# semiflex-1.net
KiCad netlist of a schematic drawn in Altium Designer
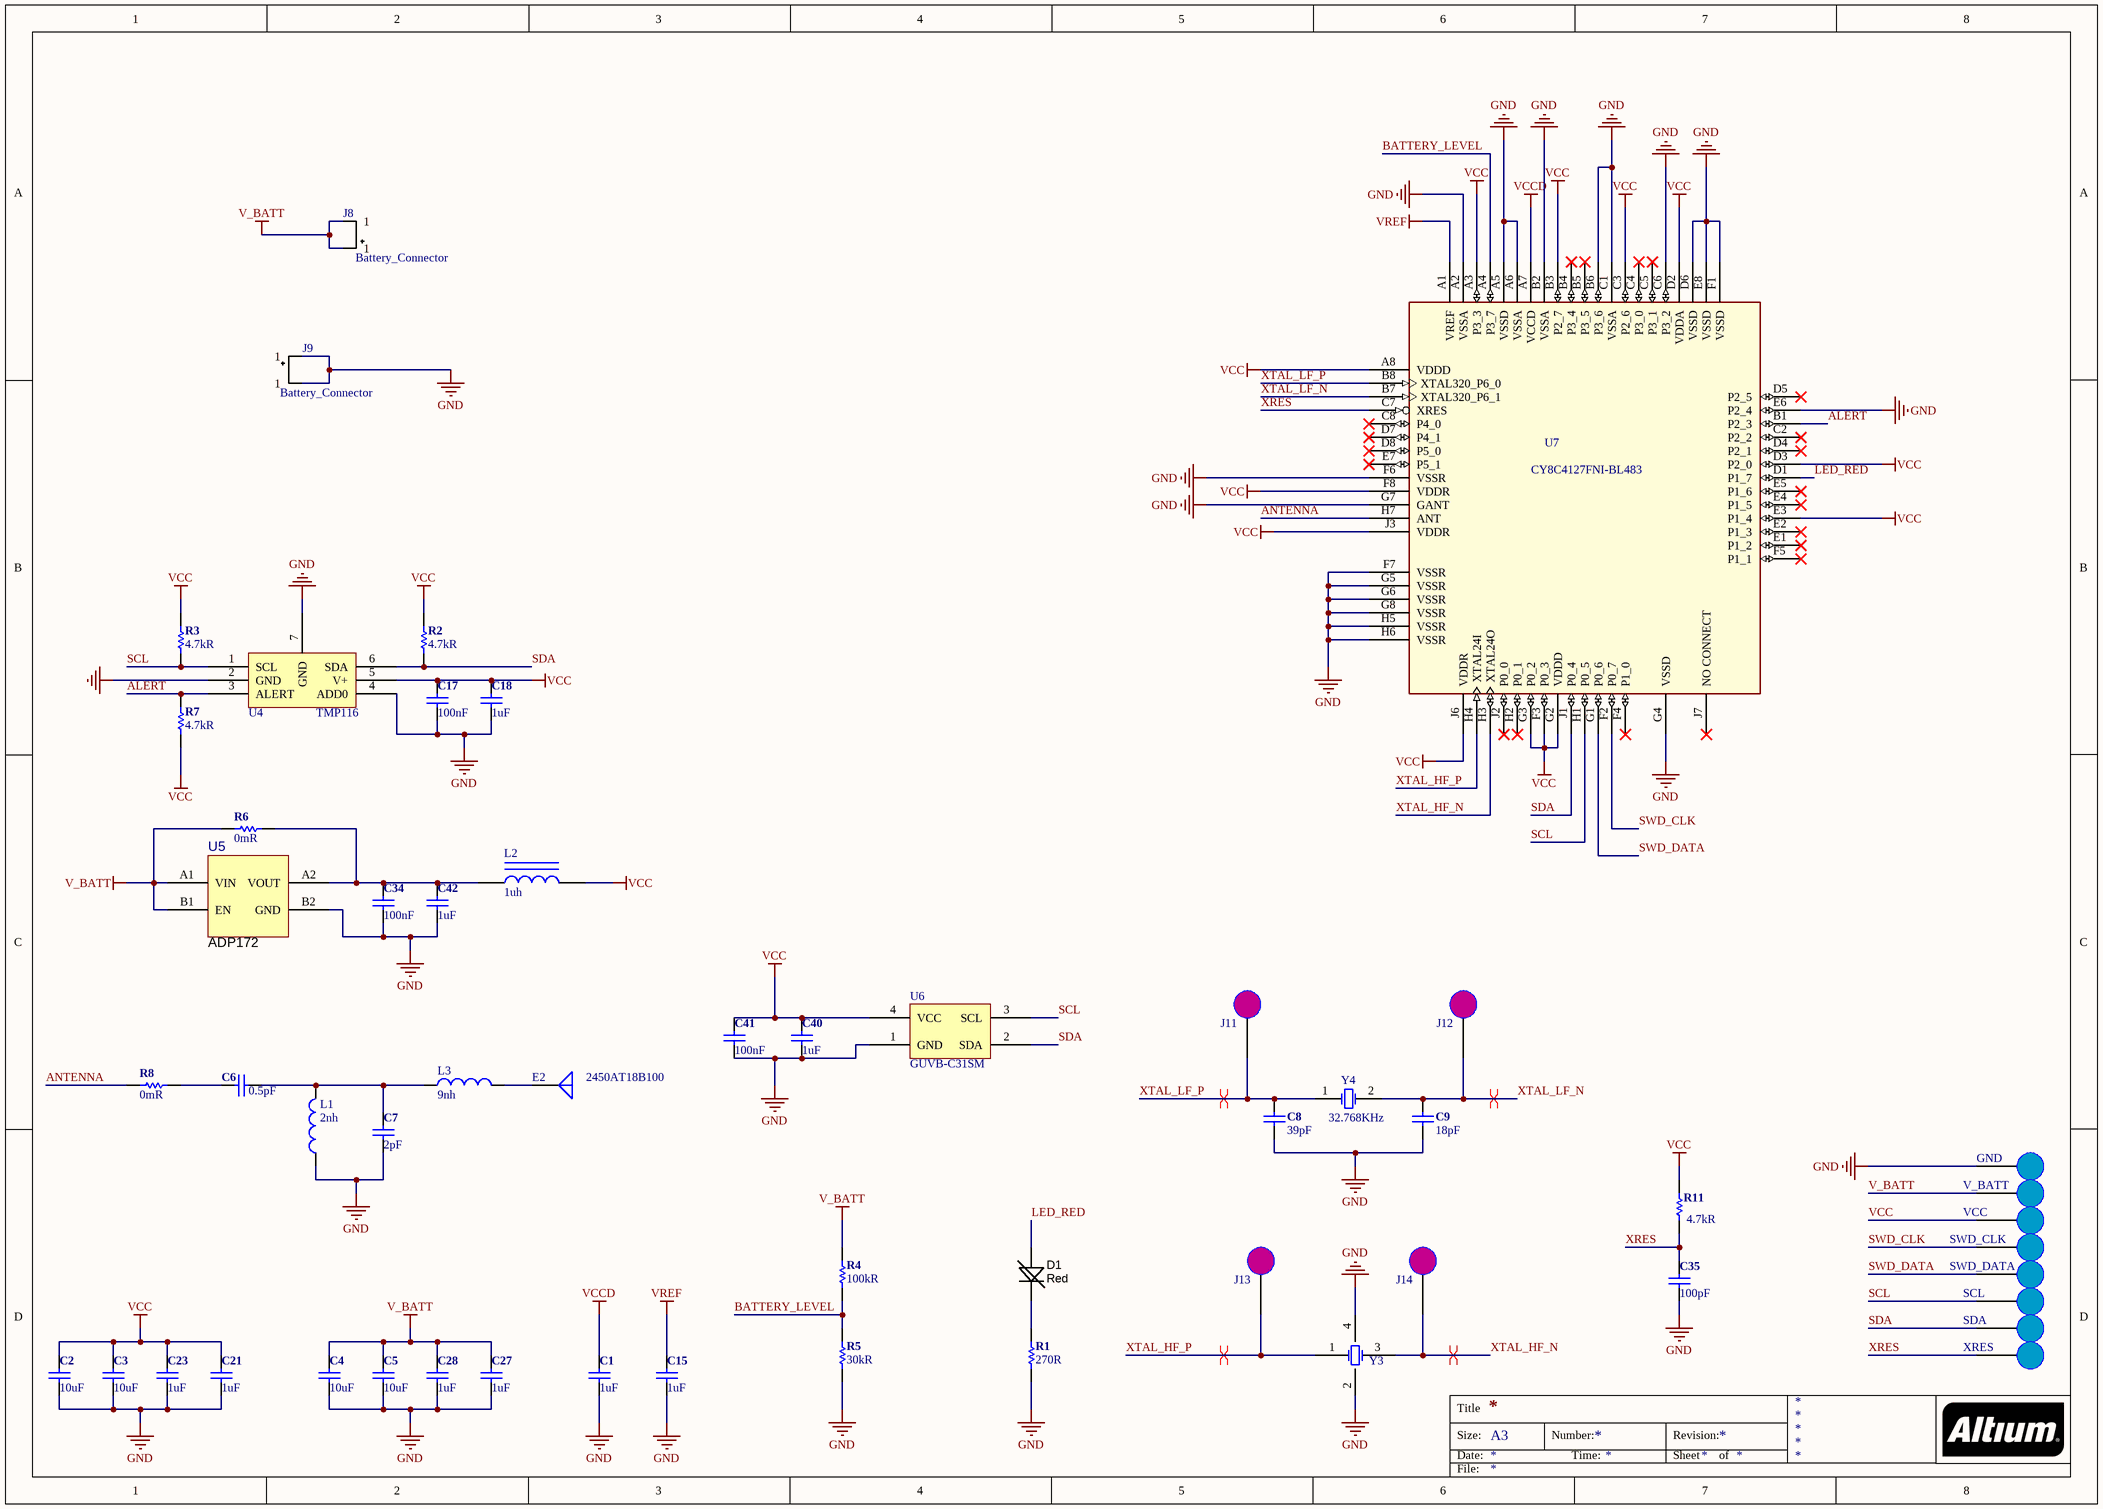
[diagram p0: semiflex-1.SchDoc]

(export (version "E")
  (design (tool "Eeschema 10.0.6"))
  (components
    (comp (ref "C1")
      (value "1uF")
      (footprint "CAP_0201(0603)_M")
      (description "___ OHM ___ mW 0201(0603) SMD")
      (fields
        (field (name "MANUFACTURER") "Murata")
        (field (name "MANUFACTURER PART NUMBER") "GRM033C81A105ME05D")
      )
      (libsource (lib "tempsensor") (part "C-0201(0603)"))
    )
    (comp (ref "C2")
      (value "10uF")
      (footprint "CAP_0402(1005)_M")
      (description "___ OHM ___ mW 0402(1005) SMD")
      (fields
        (field (name "MANUFACTURER") "Murata")
        (field (name "MANUFACTURER PART NUMBER") "GRM155R60J106ME15D")
      )
      (libsource (lib "tempsensor") (part "C-0402(1005)"))
    )
    (comp (ref "C3")
      (value "10uF")
      (footprint "CAP_0402(1005)_M")
      (description "___ OHM ___ mW 0402(1005) SMD")
      (fields
        (field (name "MANUFACTURER") "Murata")
        (field (name "MANUFACTURER PART NUMBER") "GRM155R60J106ME15D")
      )
      (libsource (lib "tempsensor") (part "C-0402(1005)"))
    )
    (comp (ref "C4")
      (value "10uF")
      (footprint "CAP_0402(1005)_M")
      (description "___ OHM ___ mW 0402(1005) SMD")
      (fields
        (field (name "MANUFACTURER") "Murata")
        (field (name "MANUFACTURER PART NUMBER") "GRM155R60J106ME15D")
      )
      (libsource (lib "tempsensor") (part "C-0402(1005)"))
    )
    (comp (ref "C5")
      (value "10uF")
      (footprint "CAP_0402(1005)_M")
      (description "___ OHM ___ mW 0402(1005) SMD")
      (fields
        (field (name "MANUFACTURER") "Murata")
        (field (name "MANUFACTURER PART NUMBER") "GRM155R60J106ME15D")
      )
      (libsource (lib "tempsensor") (part "C-0402(1005)"))
    )
    (comp (ref "C6")
      (value "0.5pF")
      (footprint "CAP_0402(1005)_M")
      (description "___ OHM ___ mW 0402(1005) SMD")
      (fields
        (field (name "MANUFACTURER") "Murata")
        (field (name "MANUFACTURER PART NUMBER") "GJM1555C1HR50WB01D")
      )
      (libsource (lib "tempsensor") (part "C-0402(1005)"))
    )
    (comp (ref "C7")
      (value "2pF")
      (footprint "CAP_0402(1005)_M")
      (description "___ OHM ___ mW 0402(1005) SMD")
      (fields
        (field (name "MANUFACTURER") "Murata")
        (field (name "MANUFACTURER PART NUMBER") "GJM1555C1H2R0BB01D")
      )
      (libsource (lib "tempsensor") (part "C-0402(1005)"))
    )
    (comp (ref "C8")
      (value "39pF")
      (footprint "CAP_0402(1005)_M")
      (description "___ OHM ___ mW 0402(1005) SMD")
      (fields
        (field (name "MANUFACTURER") "KEMET")
        (field (name "MANUFACTURER PART NUMBER") "CBR04C390F5GAC")
      )
      (libsource (lib "tempsensor") (part "C-0402(1005)"))
    )
    (comp (ref "C9")
      (value "18pF")
      (footprint "CAP_0402(1005)_M")
      (description "___ OHM ___ mW 0402(1005) SMD")
      (fields
        (field (name "MANUFACTURER") "Murata")
        (field (name "MANUFACTURER PART NUMBER") "GJM1555C1H180FB01D")
      )
      (libsource (lib "tempsensor") (part "C-0402(1005)"))
    )
    (comp (ref "C15")
      (value "1uF")
      (footprint "CAP_0201(0603)_M")
      (description "___ OHM ___ mW 0201(0603) SMD")
      (fields
        (field (name "MANUFACTURER") "Murata")
        (field (name "MANUFACTURER PART NUMBER") "GRM033C81A105ME05D")
      )
      (libsource (lib "tempsensor") (part "C-0201(0603)"))
    )
    (comp (ref "C17")
      (value "100nF")
      (footprint "CAP_0201(0603)_M")
      (description "___ OHM ___ mW 0201(0603) SMD")
      (fields
        (field (name "MANUFACTURER") "Murata")
        (field (name "MANUFACTURER PART NUMBER") "GRM033R61A104ME15D")
      )
      (libsource (lib "tempsensor") (part "C-0201(0603)"))
    )
    (comp (ref "C18")
      (value "1uF")
      (footprint "CAP_0201(0603)_M")
      (description "___ OHM ___ mW 0201(0603) SMD")
      (fields
        (field (name "MANUFACTURER") "Murata")
        (field (name "MANUFACTURER PART NUMBER") "GRM033C81A105ME05D")
      )
      (libsource (lib "tempsensor") (part "C-0201(0603)"))
    )
    (comp (ref "C21")
      (value "1uF")
      (footprint "CAP_0201(0603)_M")
      (description "___ OHM ___ mW 0201(0603) SMD")
      (fields
        (field (name "MANUFACTURER") "Murata")
        (field (name "MANUFACTURER PART NUMBER") "GRM033C81A105ME05D")
      )
      (libsource (lib "tempsensor") (part "C-0201(0603)"))
    )
    (comp (ref "C23")
      (value "1uF")
      (footprint "CAP_0201(0603)_M")
      (description "___ OHM ___ mW 0201(0603) SMD")
      (fields
        (field (name "MANUFACTURER") "Murata")
        (field (name "MANUFACTURER PART NUMBER") "GRM033C81A105ME05D")
      )
      (libsource (lib "tempsensor") (part "C-0201(0603)"))
    )
    (comp (ref "C27")
      (value "1uF")
      (footprint "CAP_0201(0603)_M")
      (description "___ OHM ___ mW 0201(0603) SMD")
      (fields
        (field (name "MANUFACTURER") "Murata")
        (field (name "MANUFACTURER PART NUMBER") "GRM033C81A105ME05D")
      )
      (libsource (lib "tempsensor") (part "C-0201(0603)"))
    )
    (comp (ref "C28")
      (value "1uF")
      (footprint "CAP_0201(0603)_M")
      (description "___ OHM ___ mW 0201(0603) SMD")
      (fields
        (field (name "MANUFACTURER") "Murata")
        (field (name "MANUFACTURER PART NUMBER") "GRM033C81A105ME05D")
      )
      (libsource (lib "tempsensor") (part "C-0201(0603)"))
    )
    (comp (ref "C34")
      (value "100nF")
      (footprint "CAP_0201(0603)_M")
      (description "___ OHM ___ mW 0201(0603) SMD")
      (fields
        (field (name "MANUFACTURER") "Murata")
        (field (name "MANUFACTURER PART NUMBER") "GRM033R61A104ME15D")
      )
      (libsource (lib "tempsensor") (part "C-0201(0603)"))
    )
    (comp (ref "C35")
      (value "100pF")
      (footprint "CAP_0201(0603)_M")
      (description "___ OHM ___ mW 0201(0603) SMD")
      (fields
        (field (name "MANUFACTURER") "Murata")
        (field (name "MANUFACTURER PART NUMBER") "GRM033R71C101KA01D")
      )
      (libsource (lib "tempsensor") (part "C-0201(0603)"))
    )
    (comp (ref "C40")
      (value "1uF")
      (footprint "CAP_0201(0603)_M")
      (description "___ OHM ___ mW 0201(0603) SMD")
      (fields
        (field (name "MANUFACTURER") "Murata")
        (field (name "MANUFACTURER PART NUMBER") "GRM033C81A105ME05D")
      )
      (libsource (lib "tempsensor") (part "C-0201(0603)"))
    )
    (comp (ref "C41")
      (value "100nF")
      (footprint "CAP_0201(0603)_M")
      (description "___ OHM ___ mW 0201(0603) SMD")
      (fields
        (field (name "MANUFACTURER") "Murata")
        (field (name "MANUFACTURER PART NUMBER") "GRM033R61A104ME15D")
      )
      (libsource (lib "tempsensor") (part "C-0201(0603)"))
    )
    (comp (ref "C42")
      (value "1uF")
      (footprint "CAP_0201(0603)_M")
      (description "___ OHM ___ mW 0201(0603) SMD")
      (fields
        (field (name "MANUFACTURER") "Murata")
        (field (name "MANUFACTURER PART NUMBER") "GRM033C81A105ME05D")
      )
      (libsource (lib "tempsensor") (part "C-0201(0603)"))
    )
    (comp (ref "D1")
      (value "Red")
      (footprint "LED_0402(1005)")
      (description "LED, 0402(1005) SMD")
      (fields
        (field (name "MANUFACTURER") "Kingbright")
        (field (name "MANUFACTURER PART NUMBER") "APHHS1005SURCK")
      )
      (libsource (lib "tempsensor") (part "LED_0402(1005)"))
    )
    (comp (ref "E2")
      (value "2450AT18B100")
      (footprint "2450AT18B100")
      (description "2.4 GHz BLE Antenna")
      (fields
        (field (name "MANUFACTURER") "Johanson")
        (field (name "MANUFACTURER PART NUMBER") "2450AT18B100E")
      )
      (libsource (lib "tempsensor") (part "2450AT18B100"))
    )
    (comp (ref "GND")
      (value "Probe-Pin Pad")
      (footprint "Pogo-Pin-Pad")
      (libsource (lib "tempsensor") (part "Probe-Pin Pad"))
    )
    (comp (ref "J8")
      (value "Battery_Connector")
      (footprint "Battery_PAD")
      (libsource (lib "tempsensor") (part "Battery_Connector"))
    )
    (comp (ref "J9")
      (value "Battery_Connector")
      (footprint "Battery_PAD")
      (libsource (lib "tempsensor") (part "Battery_Connector"))
    )
    (comp (ref "J11")
      (value "Probe-CLOCK")
      (footprint "Pogo-CLOCK-PAD")
      (libsource (lib "tempsensor") (part "Probe-CLOCK"))
    )
    (comp (ref "J12")
      (value "Probe-CLOCK")
      (footprint "Pogo-CLOCK-PAD")
      (libsource (lib "tempsensor") (part "Probe-CLOCK"))
    )
    (comp (ref "J13")
      (value "Probe-CLOCK")
      (footprint "Pogo-CLOCK-PAD")
      (libsource (lib "tempsensor") (part "Probe-CLOCK"))
    )
    (comp (ref "J14")
      (value "Probe-CLOCK")
      (footprint "Pogo-CLOCK-PAD")
      (libsource (lib "tempsensor") (part "Probe-CLOCK"))
    )
    (comp (ref "L1")
      (value "2nh")
      (footprint "IND_0402(1005)_M")
      (fields
        (field (name "MANUFACTURER") "Abracon")
        (field (name "MANUFACTURER PART NUMBER") "AISC-0402-2N0J-T")
        (field (name "TOLERANCE") "5%")
      )
      (libsource (lib "tempsensor") (part "I-0402(1005)"))
    )
    (comp (ref "L2")
      (value "1uh")
      (footprint "IND_0402(1005)_M")
      (description "Magnetic-Core Inductor")
      (fields
        (field (name "MANUFACTURER") "TDK")
        (field (name "MANUFACTURER PART NUMBER") "MLZ1005M1R0WT000")
      )
      (libsource (lib "tempsensor") (part "Inductor Iron"))
    )
    (comp (ref "L3")
      (value "9nh")
      (footprint "IND_0402(1005)_M")
      (fields
        (field (name "MANUFACTURER") "Murata")
        (field (name "MANUFACTURER PART NUMBER") "LQW15AN9N0G80D")
        (field (name "TOLERANCE") "2%")
      )
      (libsource (lib "tempsensor") (part "I-0402(1005)"))
    )
    (comp (ref "R1")
      (value "270R")
      (footprint "RES_0201(0603)_M")
      (description "___ OHM ___ mW 0201(0603) SMD")
      (fields
        (field (name "MANUFACTURER") "Yageo")
        (field (name "MANUFACTURER PART NUMBER") "RC0201JR-07270RL")
      )
      (libsource (lib "tempsensor") (part "R-0201(0603)"))
    )
    (comp (ref "R2")
      (value "4.7kR")
      (footprint "RES_0201(0603)_M")
      (description "___ OHM ___ mW 0201(0603) SMD")
      (fields
        (field (name "MANUFACTURER") "Samsung")
        (field (name "MANUFACTURER PART NUMBER") "RC0603F472CS")
      )
      (libsource (lib "tempsensor") (part "R-0201(0603)"))
    )
    (comp (ref "R3")
      (value "4.7kR")
      (footprint "RES_0201(0603)_M")
      (description "___ OHM ___ mW 0201(0603) SMD")
      (fields
        (field (name "MANUFACTURER") "Samsung")
        (field (name "MANUFACTURER PART NUMBER") "RC0603F472CS")
      )
      (libsource (lib "tempsensor") (part "R-0201(0603)"))
    )
    (comp (ref "R4")
      (value "100kR")
      (footprint "RES_0201(0603)_M")
      (description "___ OHM ___ mW 0201(0603) SMD")
      (fields
        (field (name "MANUFACTURER") "Yageo")
        (field (name "MANUFACTURER PART NUMBER") "RC0201FR-07100KL")
      )
      (libsource (lib "tempsensor") (part "R-0201(0603)"))
    )
    (comp (ref "R5")
      (value "30kR")
      (footprint "RES_0201(0603)_M")
      (description "___ OHM ___ mW 0201(0603) SMD")
      (fields
        (field (name "MANUFACTURER") "Yageo")
        (field (name "MANUFACTURER PART NUMBER") "RC0201FR-0730KL")
      )
      (libsource (lib "tempsensor") (part "R-0201(0603)"))
    )
    (comp (ref "R6")
      (value "0mR")
      (footprint "RES_0402(1005)_M")
      (description "___ OHM ___ mW 0402(1005) SMD")
      (fields
        (field (name "MANUFACTURER") "Panasonic")
        (field (name "MANUFACTURER PART NUMBER") "ERJ-2GE0R00X")
      )
      (libsource (lib "tempsensor") (part "R-0402(1005)"))
    )
    (comp (ref "R7")
      (value "4.7kR")
      (footprint "RES_0201(0603)_M")
      (description "___ OHM ___ mW 0201(0603) SMD")
      (fields
        (field (name "MANUFACTURER") "Samsung")
        (field (name "MANUFACTURER PART NUMBER") "RC0603F472CS")
      )
      (libsource (lib "tempsensor") (part "R-0201(0603)"))
    )
    (comp (ref "R8")
      (value "0mR")
      (footprint "RES_0402(1005)_M")
      (description "___ OHM ___ mW 0402(1005) SMD")
      (fields
        (field (name "MANUFACTURER") "Panasonic")
        (field (name "MANUFACTURER PART NUMBER") "ERJ-2GE0R00X")
      )
      (libsource (lib "tempsensor") (part "R-0402(1005)"))
    )
    (comp (ref "R11")
      (value "4.7kR")
      (footprint "RES_0201(0603)_M")
      (description "___ OHM ___ mW 0201(0603) SMD")
      (fields
        (field (name "MANUFACTURER") "Samsung")
        (field (name "MANUFACTURER PART NUMBER") "RC0603F472CS")
      )
      (libsource (lib "tempsensor") (part "R-0201(0603)"))
    )
    (comp (ref "SCL")
      (value "Probe-Pin Pad")
      (footprint "Pogo-Pin-Pad")
      (libsource (lib "tempsensor") (part "Probe-Pin Pad"))
    )
    (comp (ref "SDA")
      (value "Probe-Pin Pad")
      (footprint "Pogo-Pin-Pad")
      (libsource (lib "tempsensor") (part "Probe-Pin Pad"))
    )
    (comp (ref "SWD_CLK")
      (value "Probe-Pin Pad")
      (footprint "Pogo-Pin-Pad")
      (libsource (lib "tempsensor") (part "Probe-Pin Pad"))
    )
    (comp (ref "SWD_DATA")
      (value "Probe-Pin Pad")
      (footprint "Pogo-Pin-Pad")
      (libsource (lib "tempsensor") (part "Probe-Pin Pad"))
    )
    (comp (ref "U4")
      (value "TMP116")
      (footprint "WSON-6")
      (description "TI Digital I2C Temperature Sensor")
      (fields
        (field (name "MANUFACTURER") "Texas Instruments")
        (field (name "MANUFACTURER PART NUMBER") "TMP116AIDRVT")
      )
      (libsource (lib "tempsensor") (part "TMP116"))
    )
    (comp (ref "U5")
      (value "ADP172")
      (footprint "ADP172")
      (description "3V LDO")
      (fields
        (field (name "MANUFACTURER") "Analog Devices")
        (field (name "MANUFACTURER PART NUMBER") "ADP172ACBZ-3.0-R7")
      )
      (libsource (lib "tempsensor") (part "ADP172"))
    )
    (comp (ref "U6")
      (value "GUVB-C31SM")
      (footprint "GUVB-C31SM")
      (libsource (lib "tempsensor") (part "GUVB-C31SM"))
    )
    (comp (ref "U7")
      (value "CY8C4127FNI-BL483")
      (footprint "WLCSP-68_MOD")
      (description "PSOC 4 CYBLE")
      (fields
        (field (name "MANUFACTURER") "Cypress")
        (field (name "MANUFACTURER PART NUMBER") "CY8C4247FNI-BL483T")
      )
      (libsource (lib "tempsensor") (part "CY8C4127FNI-BL483"))
    )
    (comp (ref "VCC")
      (value "Probe-Pin Pad")
      (footprint "Pogo-Pin-Pad")
      (libsource (lib "tempsensor") (part "Probe-Pin Pad"))
    )
    (comp (ref "V_BATT")
      (value "Probe-Pin Pad")
      (footprint "Pogo-Pin-Pad")
      (libsource (lib "tempsensor") (part "Probe-Pin Pad"))
    )
    (comp (ref "XRES")
      (value "Probe-Pin Pad")
      (footprint "Pogo-Pin-Pad")
      (libsource (lib "tempsensor") (part "Probe-Pin Pad"))
    )
    (comp (ref "Y3")
      (value "ECX-2236")
      (footprint "ECX-2236")
      (description "24 MHz Crystal")
      (fields
        (field (name "MANUFACTURER") "ECS International")
        (field (name "MANUFACTURER PART NUMBER") "ECS-240-8-36CKM-TR")
      )
      (libsource (lib "tempsensor") (part "ECX-2236"))
    )
    (comp (ref "Y4")
      (value "32.768KHz")
      (footprint "ABS05")
      (description "Crystal Oscillator")
      (fields
        (field (name "MANUFACTURER") "Abracon")
        (field (name "MANUFACTURER PART NUMBER") "ABS05-32.768KHZ-T")
      )
      (libsource (lib "tempsensor") (part "ABS05"))
    )
  )
  (nets
    (net (code "1") (name "/ALERT") (class "Default")
      (node (ref "R7") (pin "1") (pinfunction "1_1") (pintype "passive"))
      (node (ref "U4") (pin "3") (pinfunction "ALERT_3") (pintype "passive"))
      (node (ref "U7") (pin "B1") (pinfunction "P2_3_B1") (pintype "bidirectional"))
    )
    (net (code "2") (name "/ANTENNA") (class "Default")
      (node (ref "R8") (pin "1") (pinfunction "1_1") (pintype "passive"))
      (node (ref "U7") (pin "H7") (pinfunction "ANT_H7") (pintype "passive"))
    )
    (net (code "3") (name "/BATTERY_LEVEL") (class "Default")
      (node (ref "R4") (pin "2") (pinfunction "2_2") (pintype "passive"))
      (node (ref "R5") (pin "1") (pinfunction "1_1") (pintype "passive"))
      (node (ref "U7") (pin "A4") (pinfunction "P3_7_A4") (pintype "bidirectional"))
    )
    (net (code "4") (name "/LED_RED") (class "Default")
      (node (ref "D1") (pin "A") (pinfunction "A_A") (pintype "passive"))
      (node (ref "U7") (pin "D1") (pinfunction "P1_7_D1") (pintype "bidirectional"))
    )
    (net (code "5") (name "/SCL") (class "Default")
      (node (ref "R3") (pin "2") (pinfunction "2_2") (pintype "passive"))
      (node (ref "SCL") (pin "1") (pinfunction "1_1") (pintype "passive"))
      (node (ref "U4") (pin "1") (pinfunction "SCL_1") (pintype "passive"))
      (node (ref "U6") (pin "3") (pinfunction "SCL_3") (pintype "passive"))
      (node (ref "U7") (pin "H1") (pinfunction "P0_5_H1") (pintype "bidirectional"))
    )
    (net (code "6") (name "/SDA") (class "Default")
      (node (ref "R2") (pin "2") (pinfunction "2_2") (pintype "passive"))
      (node (ref "SDA") (pin "1") (pinfunction "1_1") (pintype "passive"))
      (node (ref "U4") (pin "6") (pinfunction "SDA_6") (pintype "passive"))
      (node (ref "U6") (pin "2") (pinfunction "SDA_2") (pintype "passive"))
      (node (ref "U7") (pin "J1") (pinfunction "P0_4_J1") (pintype "bidirectional"))
    )
    (net (code "7") (name "/SWD_CLK") (class "Default")
      (node (ref "SWD_CLK") (pin "1") (pinfunction "1_1") (pintype "passive"))
      (node (ref "U7") (pin "F2") (pinfunction "P0_7_F2") (pintype "bidirectional"))
    )
    (net (code "8") (name "/SWD_DATA") (class "Default")
      (node (ref "SWD_DATA") (pin "1") (pinfunction "1_1") (pintype "passive"))
      (node (ref "U7") (pin "G1") (pinfunction "P0_6_G1") (pintype "bidirectional"))
    )
    (net (code "9") (name "/XRES") (class "Default")
      (node (ref "C35") (pin "1") (pinfunction "1_1") (pintype "passive"))
      (node (ref "R11") (pin "2") (pinfunction "2_2") (pintype "passive"))
      (node (ref "U7") (pin "C7") (pinfunction "XRES_C7") (pintype "input"))
      (node (ref "XRES") (pin "1") (pinfunction "1_1") (pintype "passive"))
    )
    (net (code "10") (name "/XTAL_HF_N") (class "Default")
      (node (ref "J14") (pin "1") (pinfunction "1_1") (pintype "passive"))
      (node (ref "U7") (pin "H3") (pinfunction "XTAL24O_H3") (pintype "bidirectional"))
      (node (ref "Y3") (pin "3") (pinfunction "OSC2_3") (pintype "passive"))
    )
    (net (code "11") (name "/XTAL_HF_P") (class "Default")
      (node (ref "J13") (pin "1") (pinfunction "1_1") (pintype "passive"))
      (node (ref "U7") (pin "H4") (pinfunction "XTAL24I_H4") (pintype "input"))
      (node (ref "Y3") (pin "1") (pinfunction "OSC1_1") (pintype "passive"))
    )
    (net (code "12") (name "/XTAL_LF_N") (class "Default")
      (node (ref "C9") (pin "1") (pinfunction "1_1") (pintype "passive"))
      (node (ref "J12") (pin "1") (pinfunction "1_1") (pintype "passive"))
      (node (ref "U7") (pin "B7") (pinfunction "XTAL320_P6_1_B7") (pintype "input"))
      (node (ref "Y4") (pin "2") (pinfunction "OSC2_2") (pintype "passive"))
    )
    (net (code "13") (name "/XTAL_LF_P") (class "Default")
      (node (ref "C8") (pin "1") (pinfunction "1_1") (pintype "passive"))
      (node (ref "J11") (pin "1") (pinfunction "1_1") (pintype "passive"))
      (node (ref "U7") (pin "B8") (pinfunction "XTAL320_P6_0_B8") (pintype "input"))
      (node (ref "Y4") (pin "1") (pinfunction "OSC1_1") (pintype "passive"))
    )
    (net (code "14") (name "GND") (class "Default")
      (node (ref "C1") (pin "2") (pinfunction "2_2") (pintype "passive"))
      (node (ref "C15") (pin "2") (pinfunction "2_2") (pintype "passive"))
      (node (ref "C17") (pin "2") (pinfunction "2_2") (pintype "passive"))
      (node (ref "C18") (pin "2") (pinfunction "2_2") (pintype "passive"))
      (node (ref "C2") (pin "2") (pinfunction "2_2") (pintype "passive"))
      (node (ref "C21") (pin "2") (pinfunction "2_2") (pintype "passive"))
      (node (ref "C23") (pin "2") (pinfunction "2_2") (pintype "passive"))
      (node (ref "C27") (pin "2") (pinfunction "2_2") (pintype "passive"))
      (node (ref "C28") (pin "2") (pinfunction "2_2") (pintype "passive"))
      (node (ref "C3") (pin "2") (pinfunction "2_2") (pintype "passive"))
      (node (ref "C34") (pin "2") (pinfunction "2_2") (pintype "passive"))
      (node (ref "C35") (pin "2") (pinfunction "2_2") (pintype "passive"))
      (node (ref "C4") (pin "2") (pinfunction "2_2") (pintype "passive"))
      (node (ref "C40") (pin "1") (pinfunction "1_1") (pintype "passive"))
      (node (ref "C41") (pin "1") (pinfunction "1_1") (pintype "passive"))
      (node (ref "C42") (pin "2") (pinfunction "2_2") (pintype "passive"))
      (node (ref "C5") (pin "2") (pinfunction "2_2") (pintype "passive"))
      (node (ref "C7") (pin "2") (pinfunction "2_2") (pintype "passive"))
      (node (ref "C8") (pin "2") (pinfunction "2_2") (pintype "passive"))
      (node (ref "C9") (pin "2") (pinfunction "2_2") (pintype "passive"))
      (node (ref "GND") (pin "1") (pinfunction "1_1") (pintype "passive"))
      (node (ref "J9") (pin "1") (pinfunction "1_1") (pintype "passive"))
      (node (ref "L1") (pin "1") (pinfunction "1_1") (pintype "passive"))
      (node (ref "R1") (pin "2") (pinfunction "2_2") (pintype "passive"))
      (node (ref "R5") (pin "2") (pinfunction "2_2") (pintype "passive"))
      (node (ref "U4") (pin "2") (pinfunction "GND_2") (pintype "passive"))
      (node (ref "U4") (pin "4") (pinfunction "ADD0_4") (pintype "passive"))
      (node (ref "U4") (pin "7") (pinfunction "GND_7") (pintype "passive"))
      (node (ref "U5") (pin "B2") (pinfunction "GND_B2") (pintype "passive"))
      (node (ref "U6") (pin "1") (pinfunction "GND_1") (pintype "passive"))
      (node (ref "U7") (pin "A2") (pinfunction "VSSA_A2") (pintype "power_in"))
      (node (ref "U7") (pin "A5") (pinfunction "VSSD_A5") (pintype "power_in"))
      (node (ref "U7") (pin "A6") (pinfunction "VSSA_A6") (pintype "power_in"))
      (node (ref "U7") (pin "B2") (pinfunction "VSSA_B2") (pintype "power_in"))
      (node (ref "U7") (pin "B6") (pinfunction "P3_6_B6") (pintype "bidirectional"))
      (node (ref "U7") (pin "C1") (pinfunction "VSSA_C1") (pintype "power_in"))
      (node (ref "U7") (pin "C6") (pinfunction "P3_2_C6") (pintype "bidirectional"))
      (node (ref "U7") (pin "D6") (pinfunction "VSSD_D6") (pintype "power_in"))
      (node (ref "U7") (pin "E6") (pinfunction "P2_4_E6") (pintype "bidirectional"))
      (node (ref "U7") (pin "E8") (pinfunction "VSSD_E8") (pintype "power_in"))
      (node (ref "U7") (pin "F1") (pinfunction "VSSD_F1") (pintype "power_in"))
      (node (ref "U7") (pin "F6") (pinfunction "VSSR_F6") (pintype "power_in"))
      (node (ref "U7") (pin "F7") (pinfunction "VSSR_F7") (pintype "power_in"))
      (node (ref "U7") (pin "G4") (pinfunction "VSSD_G4") (pintype "power_in"))
      (node (ref "U7") (pin "G5") (pinfunction "VSSR_G5") (pintype "power_in"))
      (node (ref "U7") (pin "G6") (pinfunction "VSSR_G6") (pintype "power_in"))
      (node (ref "U7") (pin "G7") (pinfunction "GANT_G7") (pintype "power_in"))
      (node (ref "U7") (pin "G8") (pinfunction "VSSR_G8") (pintype "power_in"))
      (node (ref "U7") (pin "H5") (pinfunction "VSSR_H5") (pintype "power_in"))
      (node (ref "U7") (pin "H6") (pinfunction "VSSR_H6") (pintype "power_in"))
      (node (ref "Y3") (pin "2") (pinfunction "GND_2") (pintype "passive"))
      (node (ref "Y3") (pin "4") (pinfunction "GND_4") (pintype "passive"))
    )
    (net (code "15") (name "Net-(C6-Pad1)") (class "Default")
      (node (ref "C6") (pin "1") (pinfunction "1_1") (pintype "passive"))
      (node (ref "R8") (pin "2") (pinfunction "2_2") (pintype "passive"))
    )
    (net (code "16") (name "Net-(C6-Pad2)") (class "Default")
      (node (ref "C6") (pin "2") (pinfunction "2_2") (pintype "passive"))
      (node (ref "C7") (pin "1") (pinfunction "1_1") (pintype "passive"))
      (node (ref "L1") (pin "2") (pinfunction "2_2") (pintype "passive"))
      (node (ref "L3") (pin "1") (pinfunction "1_1") (pintype "passive"))
    )
    (net (code "17") (name "Net-(D1-PadK)") (class "Default")
      (node (ref "D1") (pin "K") (pinfunction "K_K") (pintype "passive"))
      (node (ref "R1") (pin "1") (pinfunction "1_1") (pintype "passive"))
    )
    (net (code "18") (name "Net-(E2-A)") (class "Default")
      (node (ref "E2") (pin "1") (pinfunction "A_1") (pintype "passive"))
      (node (ref "L3") (pin "2") (pinfunction "2_2") (pintype "passive"))
    )
    (net (code "19") (name "Net-(U5-VOUT)") (class "Default")
      (node (ref "C34") (pin "1") (pinfunction "1_1") (pintype "passive"))
      (node (ref "C42") (pin "1") (pinfunction "1_1") (pintype "passive"))
      (node (ref "L2") (pin "1") (pinfunction "1_1") (pintype "passive"))
      (node (ref "R6") (pin "2") (pinfunction "2_2") (pintype "passive"))
      (node (ref "U5") (pin "A2") (pinfunction "VOUT_A2") (pintype "passive"))
    )
    (net (code "20") (name "VCC") (class "Default")
      (node (ref "C17") (pin "1") (pinfunction "1_1") (pintype "passive"))
      (node (ref "C18") (pin "1") (pinfunction "1_1") (pintype "passive"))
      (node (ref "C2") (pin "1") (pinfunction "1_1") (pintype "passive"))
      (node (ref "C21") (pin "1") (pinfunction "1_1") (pintype "passive"))
      (node (ref "C23") (pin "1") (pinfunction "1_1") (pintype "passive"))
      (node (ref "C3") (pin "1") (pinfunction "1_1") (pintype "passive"))
      (node (ref "C40") (pin "2") (pinfunction "2_2") (pintype "passive"))
      (node (ref "C41") (pin "2") (pinfunction "2_2") (pintype "passive"))
      (node (ref "L2") (pin "2") (pinfunction "2_2") (pintype "passive"))
      (node (ref "R11") (pin "1") (pinfunction "1_1") (pintype "passive"))
      (node (ref "R2") (pin "1") (pinfunction "1_1") (pintype "passive"))
      (node (ref "R3") (pin "1") (pinfunction "1_1") (pintype "passive"))
      (node (ref "R7") (pin "2") (pinfunction "2_2") (pintype "passive"))
      (node (ref "U4") (pin "5") (pinfunction "V+_5") (pintype "passive"))
      (node (ref "U6") (pin "4") (pinfunction "VCC_4") (pintype "passive"))
      (node (ref "U7") (pin "A3") (pinfunction "P3_3_A3") (pintype "bidirectional"))
      (node (ref "U7") (pin "A8") (pinfunction "VDDD_A8") (pintype "power_in"))
      (node (ref "U7") (pin "B3") (pinfunction "P2_7_B3") (pintype "bidirectional"))
      (node (ref "U7") (pin "C3") (pinfunction "P2_6_C3") (pintype "bidirectional"))
      (node (ref "U7") (pin "D2") (pinfunction "VDDA_D2") (pintype "power_in"))
      (node (ref "U7") (pin "D3") (pinfunction "P2_0_D3") (pintype "bidirectional"))
      (node (ref "U7") (pin "E3") (pinfunction "P1_4_E3") (pintype "bidirectional"))
      (node (ref "U7") (pin "F3") (pinfunction "P0_3_F3") (pintype "bidirectional"))
      (node (ref "U7") (pin "F8") (pinfunction "VDDR_F8") (pintype "power_in"))
      (node (ref "U7") (pin "G2") (pinfunction "VDDD_G2") (pintype "power_in"))
      (node (ref "U7") (pin "G3") (pinfunction "P0_2_G3") (pintype "bidirectional"))
      (node (ref "U7") (pin "J3") (pinfunction "VDDR_J3") (pintype "power_in"))
      (node (ref "U7") (pin "J6") (pinfunction "VDDR_J6") (pintype "power_in"))
      (node (ref "VCC") (pin "1") (pinfunction "1_1") (pintype "passive"))
    )
    (net (code "21") (name "VCCD") (class "Default")
      (node (ref "C1") (pin "1") (pinfunction "1_1") (pintype "passive"))
      (node (ref "U7") (pin "A7") (pinfunction "VCCD_A7") (pintype "power_in"))
    )
    (net (code "22") (name "VREF") (class "Default")
      (node (ref "C15") (pin "1") (pinfunction "1_1") (pintype "passive"))
      (node (ref "U7") (pin "A1") (pinfunction "VREF_A1") (pintype "power_in"))
    )
    (net (code "23") (name "V_BATT") (class "Default")
      (node (ref "C27") (pin "1") (pinfunction "1_1") (pintype "passive"))
      (node (ref "C28") (pin "1") (pinfunction "1_1") (pintype "passive"))
      (node (ref "C4") (pin "1") (pinfunction "1_1") (pintype "passive"))
      (node (ref "C5") (pin "1") (pinfunction "1_1") (pintype "passive"))
      (node (ref "J8") (pin "1") (pinfunction "1_1") (pintype "passive"))
      (node (ref "R4") (pin "1") (pinfunction "1_1") (pintype "passive"))
      (node (ref "R6") (pin "1") (pinfunction "1_1") (pintype "passive"))
      (node (ref "U5") (pin "A1") (pinfunction "VIN_A1") (pintype "passive"))
      (node (ref "U5") (pin "B1") (pinfunction "EN_B1") (pintype "passive"))
      (node (ref "V_BATT") (pin "1") (pinfunction "1_1") (pintype "passive"))
    )
    (net (code "24") (name "unconnected-(U7-NO_CONNECT-PadJ7)") (class "Default")
      (node (ref "U7") (pin "J7") (pinfunction "NO_CONNECT_J7") (pintype "passive+no_connect"))
    )
    (net (code "25") (name "unconnected-(U7-P0_0-PadJ2)") (class "Default")
      (node (ref "U7") (pin "J2") (pinfunction "P0_0_J2") (pintype "bidirectional+no_connect"))
    )
    (net (code "26") (name "unconnected-(U7-P0_1-PadH2)") (class "Default")
      (node (ref "U7") (pin "H2") (pinfunction "P0_1_H2") (pintype "bidirectional+no_connect"))
    )
    (net (code "27") (name "unconnected-(U7-P1_0-PadF4)") (class "Default")
      (node (ref "U7") (pin "F4") (pinfunction "P1_0_F4") (pintype "bidirectional+no_connect"))
    )
    (net (code "28") (name "unconnected-(U7-P1_1-PadF5)") (class "Default")
      (node (ref "U7") (pin "F5") (pinfunction "P1_1_F5") (pintype "bidirectional+no_connect"))
    )
    (net (code "29") (name "unconnected-(U7-P1_2-PadE1)") (class "Default")
      (node (ref "U7") (pin "E1") (pinfunction "P1_2_E1") (pintype "bidirectional+no_connect"))
    )
    (net (code "30") (name "unconnected-(U7-P1_3-PadE2)") (class "Default")
      (node (ref "U7") (pin "E2") (pinfunction "P1_3_E2") (pintype "bidirectional+no_connect"))
    )
    (net (code "31") (name "unconnected-(U7-P1_5-PadE4)") (class "Default")
      (node (ref "U7") (pin "E4") (pinfunction "P1_5_E4") (pintype "bidirectional+no_connect"))
    )
    (net (code "32") (name "unconnected-(U7-P1_6-PadE5)") (class "Default")
      (node (ref "U7") (pin "E5") (pinfunction "P1_6_E5") (pintype "bidirectional+no_connect"))
    )
    (net (code "33") (name "unconnected-(U7-P2_1-PadD4)") (class "Default")
      (node (ref "U7") (pin "D4") (pinfunction "P2_1_D4") (pintype "bidirectional+no_connect"))
    )
    (net (code "34") (name "unconnected-(U7-P2_2-PadC2)") (class "Default")
      (node (ref "U7") (pin "C2") (pinfunction "P2_2_C2") (pintype "bidirectional+no_connect"))
    )
    (net (code "35") (name "unconnected-(U7-P2_5-PadD5)") (class "Default")
      (node (ref "U7") (pin "D5") (pinfunction "P2_5_D5") (pintype "bidirectional+no_connect"))
    )
    (net (code "36") (name "unconnected-(U7-P3_0-PadC4)") (class "Default")
      (node (ref "U7") (pin "C4") (pinfunction "P3_0_C4") (pintype "bidirectional+no_connect"))
    )
    (net (code "37") (name "unconnected-(U7-P3_1-PadC5)") (class "Default")
      (node (ref "U7") (pin "C5") (pinfunction "P3_1_C5") (pintype "bidirectional+no_connect"))
    )
    (net (code "38") (name "unconnected-(U7-P3_4-PadB4)") (class "Default")
      (node (ref "U7") (pin "B4") (pinfunction "P3_4_B4") (pintype "bidirectional+no_connect"))
    )
    (net (code "39") (name "unconnected-(U7-P3_5-PadB5)") (class "Default")
      (node (ref "U7") (pin "B5") (pinfunction "P3_5_B5") (pintype "bidirectional+no_connect"))
    )
    (net (code "40") (name "unconnected-(U7-P4_0-PadC8)") (class "Default")
      (node (ref "U7") (pin "C8") (pinfunction "P4_0_C8") (pintype "bidirectional+no_connect"))
    )
    (net (code "41") (name "unconnected-(U7-P4_1-PadD7)") (class "Default")
      (node (ref "U7") (pin "D7") (pinfunction "P4_1_D7") (pintype "bidirectional+no_connect"))
    )
    (net (code "42") (name "unconnected-(U7-P5_0-PadD8)") (class "Default")
      (node (ref "U7") (pin "D8") (pinfunction "P5_0_D8") (pintype "bidirectional+no_connect"))
    )
    (net (code "43") (name "unconnected-(U7-P5_1-PadE7)") (class "Default")
      (node (ref "U7") (pin "E7") (pinfunction "P5_1_E7") (pintype "bidirectional+no_connect"))
    )
  )
)
